# NEOBoard_V4.net
KiCad netlist of a schematic drawn in EAGLE
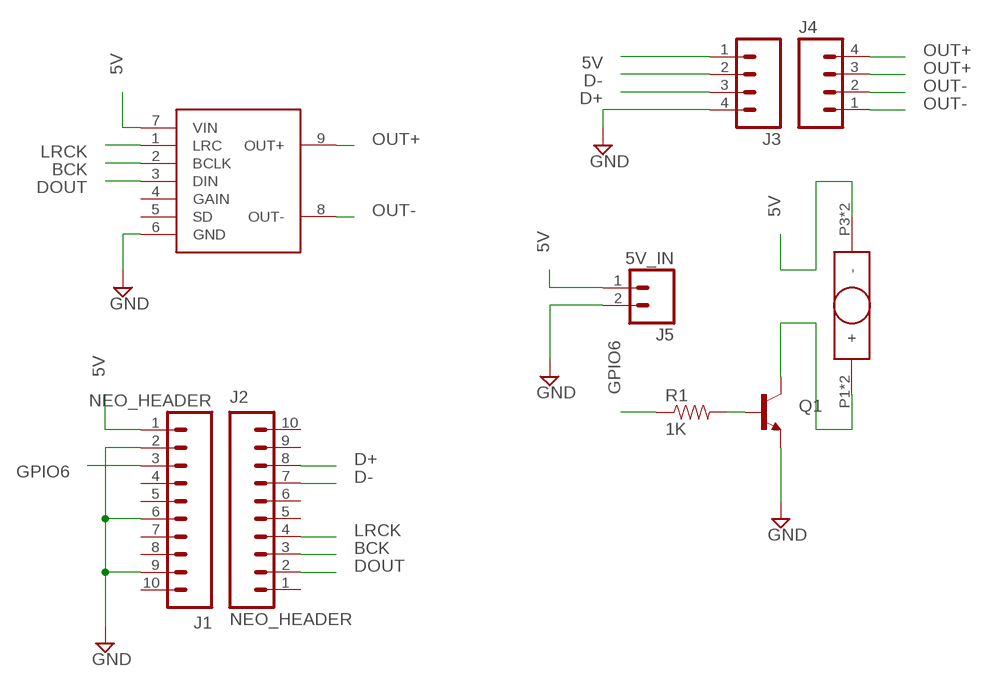
[diagram p0: schematic, sheet 1]

(export (version "E")
  (design (tool "Eeschema 10.0.6"))
  (components
    (comp (ref "J1")
      (value "NEO_HEADER")
      (footprint "eagle-import:1X10_NO_SILK")
      (libsource (lib "eagle-import") (part "M10NO_SILK_PTH_FEMALE"))
    )
    (comp (ref "J2")
      (value "NEO_HEADER")
      (footprint "eagle-import:1X10_NO_SILK")
      (libsource (lib "eagle-import") (part "M10NO_SILK_PTH_FEMALE"))
    )
    (comp (ref "J3")
      (value "M04NO_SILK_ALL_ROUND")
      (footprint "eagle-import:1X04_NO_SILK_ALL_ROUND")
      (libsource (lib "eagle-import") (part "M04NO_SILK_ALL_ROUND"))
    )
    (comp (ref "J4")
      (value "M04NO_SILK_ALL_ROUND")
      (footprint "eagle-import:1X04_NO_SILK_ALL_ROUND")
      (libsource (lib "eagle-import") (part "M04NO_SILK_ALL_ROUND"))
    )
    (comp (ref "J5")
      (value "5V_IN")
      (footprint "eagle-import:1X02_NO_SILK")
      (libsource (lib "eagle-import") (part "M021X02_NO_SILK"))
    )
    (comp (ref "Q1")
      (value "TRANSISTOR_NPNTO92")
      (footprint "eagle-import:TO-92")
      (libsource (lib "eagle-import") (part "TRANSISTOR_NPNTO92"))
    )
    (comp (ref "R1")
      (value "1K")
      (footprint "eagle-import:AXIAL-0.3")
      (libsource (lib "eagle-import") (part "1KOHM-1/4W-1%(PTH)"))
    )
    (comp (ref "U$1")
      (value "I2S_BREAKOUT")
      (footprint "eagle-import:I2S_BREAKOUT")
      (libsource (lib "eagle-import") (part "I2S_BREAKOUT"))
    )
    (comp (ref "U$2")
      (value "FUSER")
      (footprint "eagle-import:FUSE")
      (libsource (lib "eagle-import") (part "FUSER"))
    )
  )
  (nets
    (net (code "1") (name "/5V") (class "Default")
      (node (ref "J1") (pin "1") (pinfunction "1_1") (pintype "passive"))
      (node (ref "J3") (pin "1") (pinfunction "1_1") (pintype "passive"))
      (node (ref "J5") (pin "1") (pinfunction "1_1") (pintype "passive"))
      (node (ref "U$1") (pin "7") (pinfunction "VIN_7") (pintype "bidirectional"))
      (node (ref "U$2") (pin "P3") (pinfunction "-_P3") (pintype "bidirectional"))
      (node (ref "U$2") (pin "P4") (pinfunction "-_P4") (pintype "bidirectional"))
    )
    (net (code "2") (name "/BCK") (class "Default")
      (node (ref "J2") (pin "3") (pinfunction "3_3") (pintype "passive"))
      (node (ref "U$1") (pin "2") (pinfunction "BCLK_2") (pintype "bidirectional"))
    )
    (net (code "3") (name "/D+") (class "Default")
      (node (ref "J2") (pin "8") (pinfunction "8_8") (pintype "passive"))
      (node (ref "J3") (pin "3") (pinfunction "3_3") (pintype "passive"))
    )
    (net (code "4") (name "/D-") (class "Default")
      (node (ref "J2") (pin "7") (pinfunction "7_7") (pintype "passive"))
      (node (ref "J3") (pin "2") (pinfunction "2_2") (pintype "passive"))
    )
    (net (code "5") (name "/DOUT") (class "Default")
      (node (ref "J2") (pin "2") (pinfunction "2_2") (pintype "passive"))
      (node (ref "U$1") (pin "3") (pinfunction "DIN_3") (pintype "bidirectional"))
    )
    (net (code "6") (name "/GPIO6") (class "Default")
      (node (ref "J1") (pin "3") (pinfunction "3_3") (pintype "passive"))
      (node (ref "R1") (pin "P$1") (pinfunction "1_P$1") (pintype "passive"))
    )
    (net (code "7") (name "/LRCK") (class "Default")
      (node (ref "J2") (pin "4") (pinfunction "4_4") (pintype "passive"))
      (node (ref "U$1") (pin "1") (pinfunction "LRC_1") (pintype "bidirectional"))
    )
    (net (code "8") (name "/OUT+") (class "Default")
      (node (ref "J4") (pin "3") (pinfunction "3_3") (pintype "passive"))
      (node (ref "J4") (pin "4") (pinfunction "4_4") (pintype "passive"))
      (node (ref "U$1") (pin "9") (pinfunction "OUT+_9") (pintype "bidirectional"))
    )
    (net (code "9") (name "/OUT-") (class "Default")
      (node (ref "J4") (pin "1") (pinfunction "1_1") (pintype "passive"))
      (node (ref "J4") (pin "2") (pinfunction "2_2") (pintype "passive"))
      (node (ref "U$1") (pin "8") (pinfunction "OUT-_8") (pintype "bidirectional"))
    )
    (net (code "10") (name "GND") (class "Default")
      (node (ref "J1") (pin "2") (pinfunction "2_2") (pintype "passive"))
      (node (ref "J1") (pin "6") (pinfunction "6_6") (pintype "passive"))
      (node (ref "J1") (pin "9") (pinfunction "9_9") (pintype "passive"))
      (node (ref "J3") (pin "4") (pinfunction "4_4") (pintype "passive"))
      (node (ref "J5") (pin "2") (pinfunction "2_2") (pintype "passive"))
      (node (ref "Q1") (pin "1") (pinfunction "E_1") (pintype "passive"))
      (node (ref "U$1") (pin "6") (pinfunction "GND_6") (pintype "bidirectional"))
    )
    (net (code "11") (name "Net-(Q1-B)") (class "Default")
      (node (ref "Q1") (pin "2") (pinfunction "B_2") (pintype "passive"))
      (node (ref "R1") (pin "P$2") (pinfunction "2_P$2") (pintype "passive"))
    )
    (net (code "12") (name "Net-(Q1-C)") (class "Default")
      (node (ref "Q1") (pin "3") (pinfunction "C_3") (pintype "passive"))
      (node (ref "U$2") (pin "P1") (pinfunction "+_P1") (pintype "bidirectional"))
      (node (ref "U$2") (pin "P2") (pinfunction "+_P2") (pintype "bidirectional"))
    )
    (net (code "13") (name "unconnected-(J1-Pad4)") (class "Default")
      (node (ref "J1") (pin "4") (pinfunction "4_4") (pintype "passive"))
    )
    (net (code "14") (name "unconnected-(J1-Pad5)") (class "Default")
      (node (ref "J1") (pin "5") (pinfunction "5_5") (pintype "passive"))
    )
    (net (code "15") (name "unconnected-(J1-Pad7)") (class "Default")
      (node (ref "J1") (pin "7") (pinfunction "7_7") (pintype "passive"))
    )
    (net (code "16") (name "unconnected-(J1-Pad8)") (class "Default")
      (node (ref "J1") (pin "8") (pinfunction "8_8") (pintype "passive"))
    )
    (net (code "17") (name "unconnected-(J1-Pad10)") (class "Default")
      (node (ref "J1") (pin "10") (pinfunction "10_10") (pintype "passive"))
    )
    (net (code "18") (name "unconnected-(J2-Pad1)") (class "Default")
      (node (ref "J2") (pin "1") (pinfunction "1_1") (pintype "passive"))
    )
    (net (code "19") (name "unconnected-(J2-Pad5)") (class "Default")
      (node (ref "J2") (pin "5") (pinfunction "5_5") (pintype "passive"))
    )
    (net (code "20") (name "unconnected-(J2-Pad6)") (class "Default")
      (node (ref "J2") (pin "6") (pinfunction "6_6") (pintype "passive"))
    )
    (net (code "21") (name "unconnected-(J2-Pad9)") (class "Default")
      (node (ref "J2") (pin "9") (pinfunction "9_9") (pintype "passive"))
    )
    (net (code "22") (name "unconnected-(J2-Pad10)") (class "Default")
      (node (ref "J2") (pin "10") (pinfunction "10_10") (pintype "passive"))
    )
    (net (code "23") (name "unconnected-(U$1-GAIN-Pad4)") (class "Default")
      (node (ref "U$1") (pin "4") (pinfunction "GAIN_4") (pintype "bidirectional"))
    )
    (net (code "24") (name "unconnected-(U$1-SD-Pad5)") (class "Default")
      (node (ref "U$1") (pin "5") (pinfunction "SD_5") (pintype "bidirectional"))
    )
  )
)
